# synchronizer_v1_0.net
KiCad netlist of a schematic drawn in EAGLE
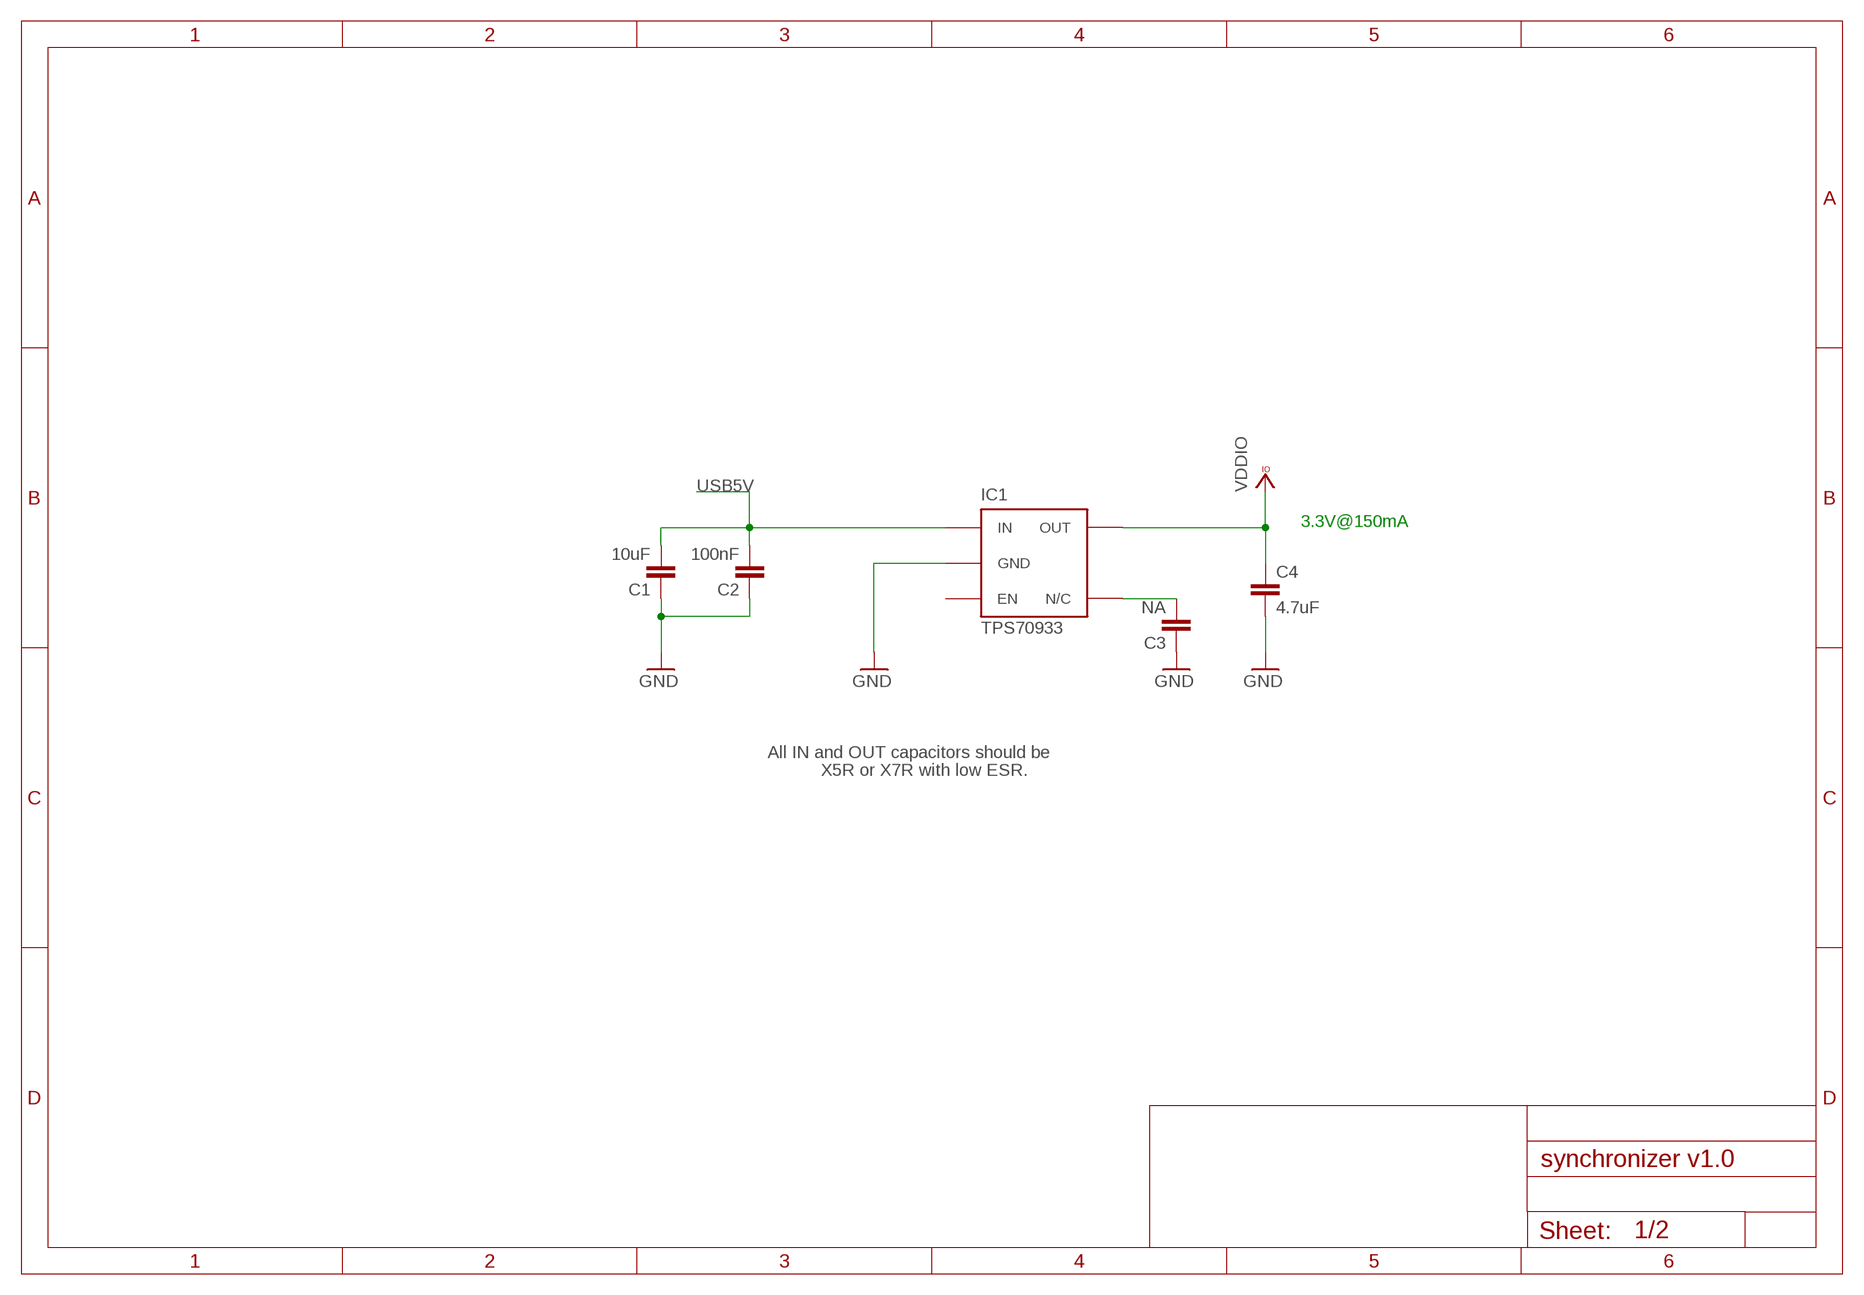
[diagram p0: schematic, sheet 1]
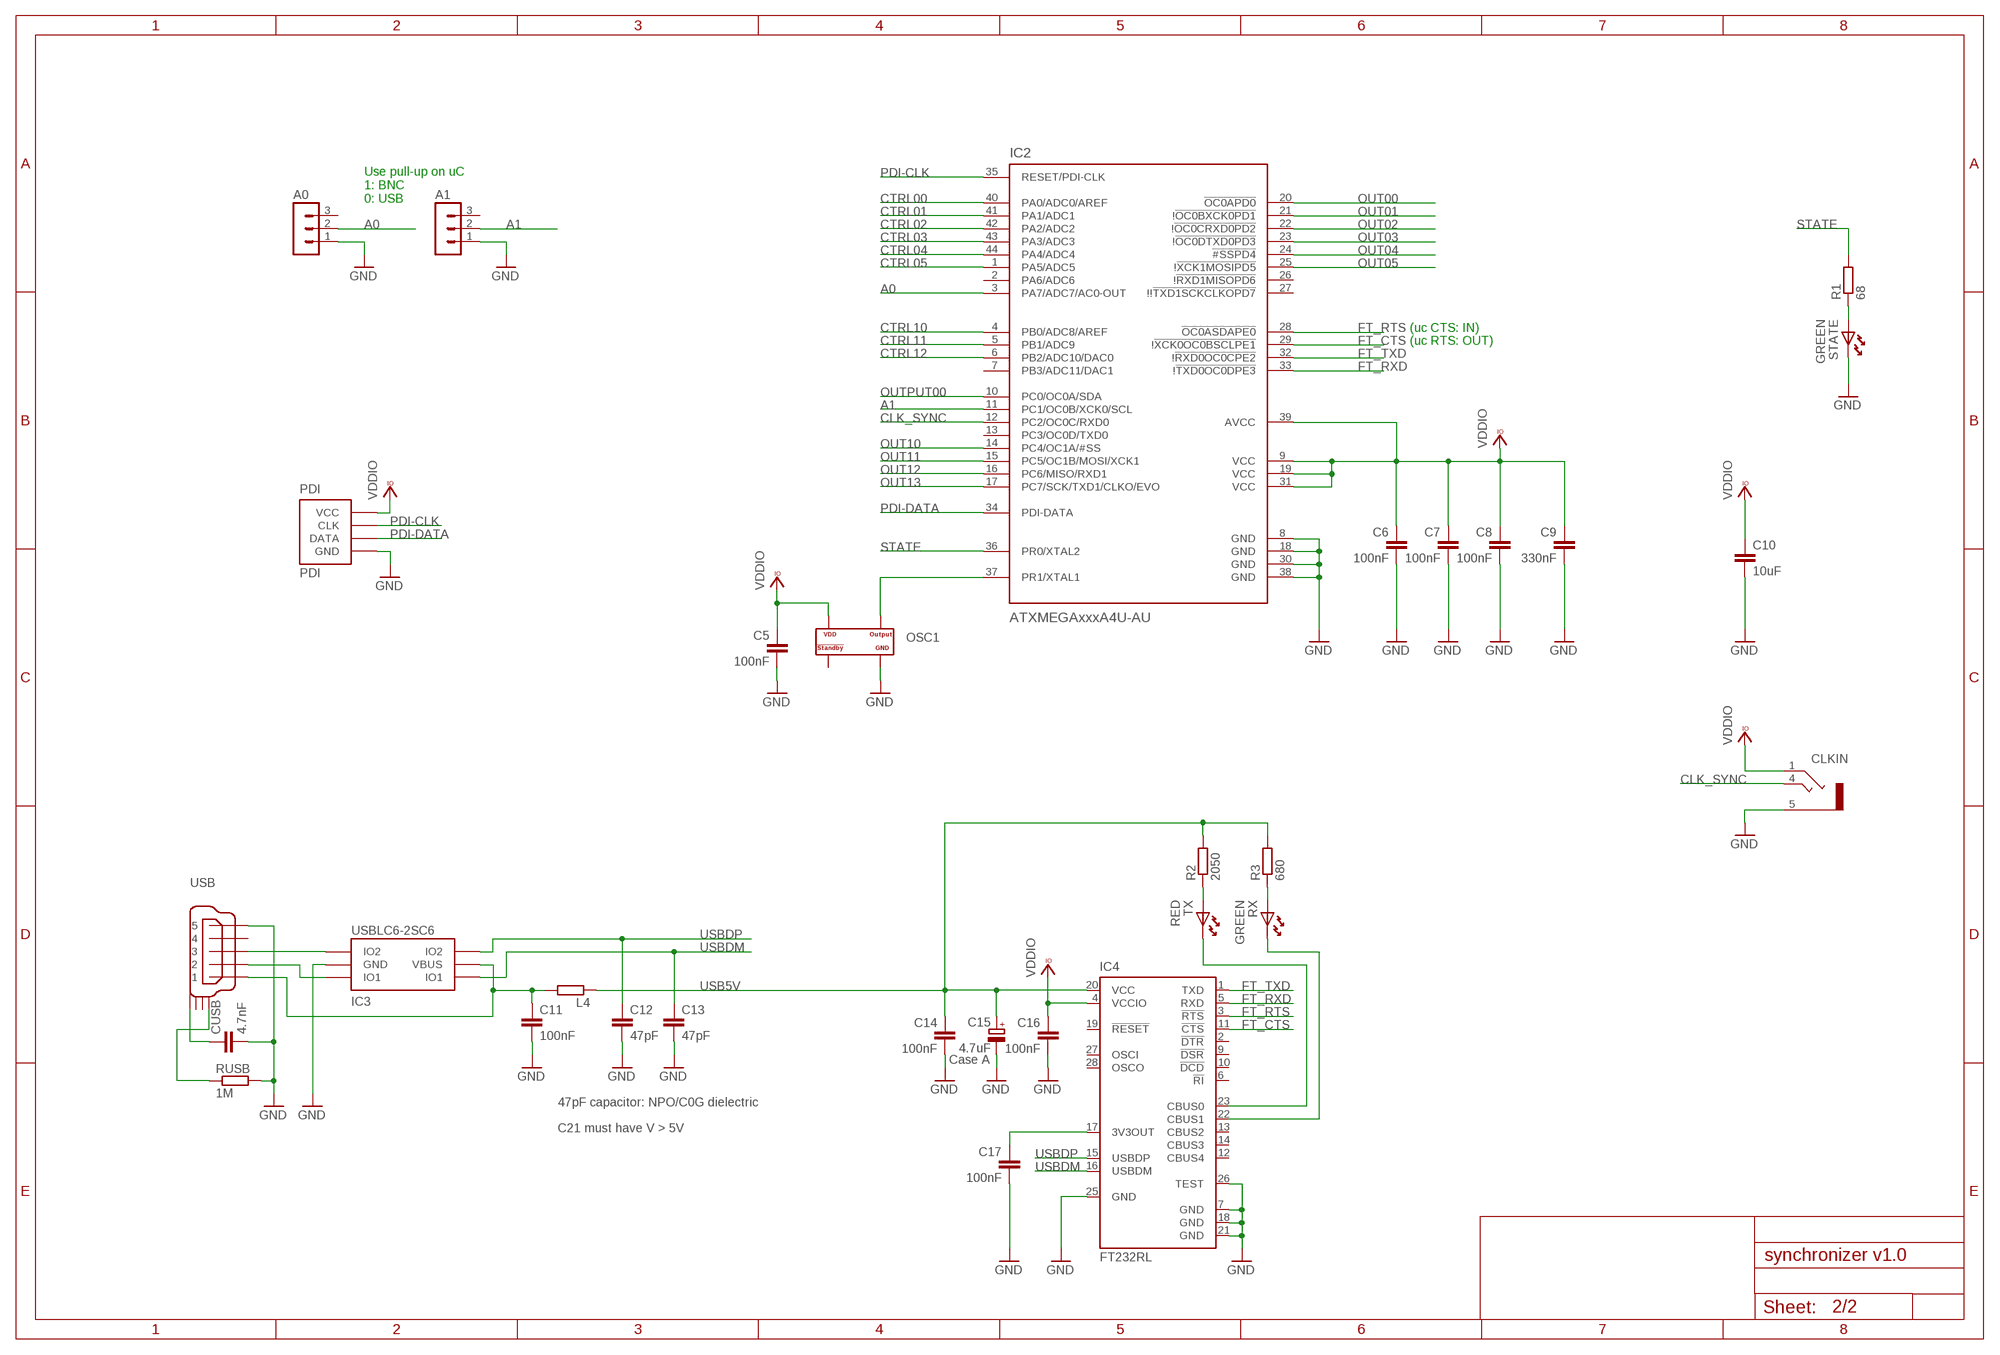
[diagram p1: schematic, sheet 2, part 1 of 2]
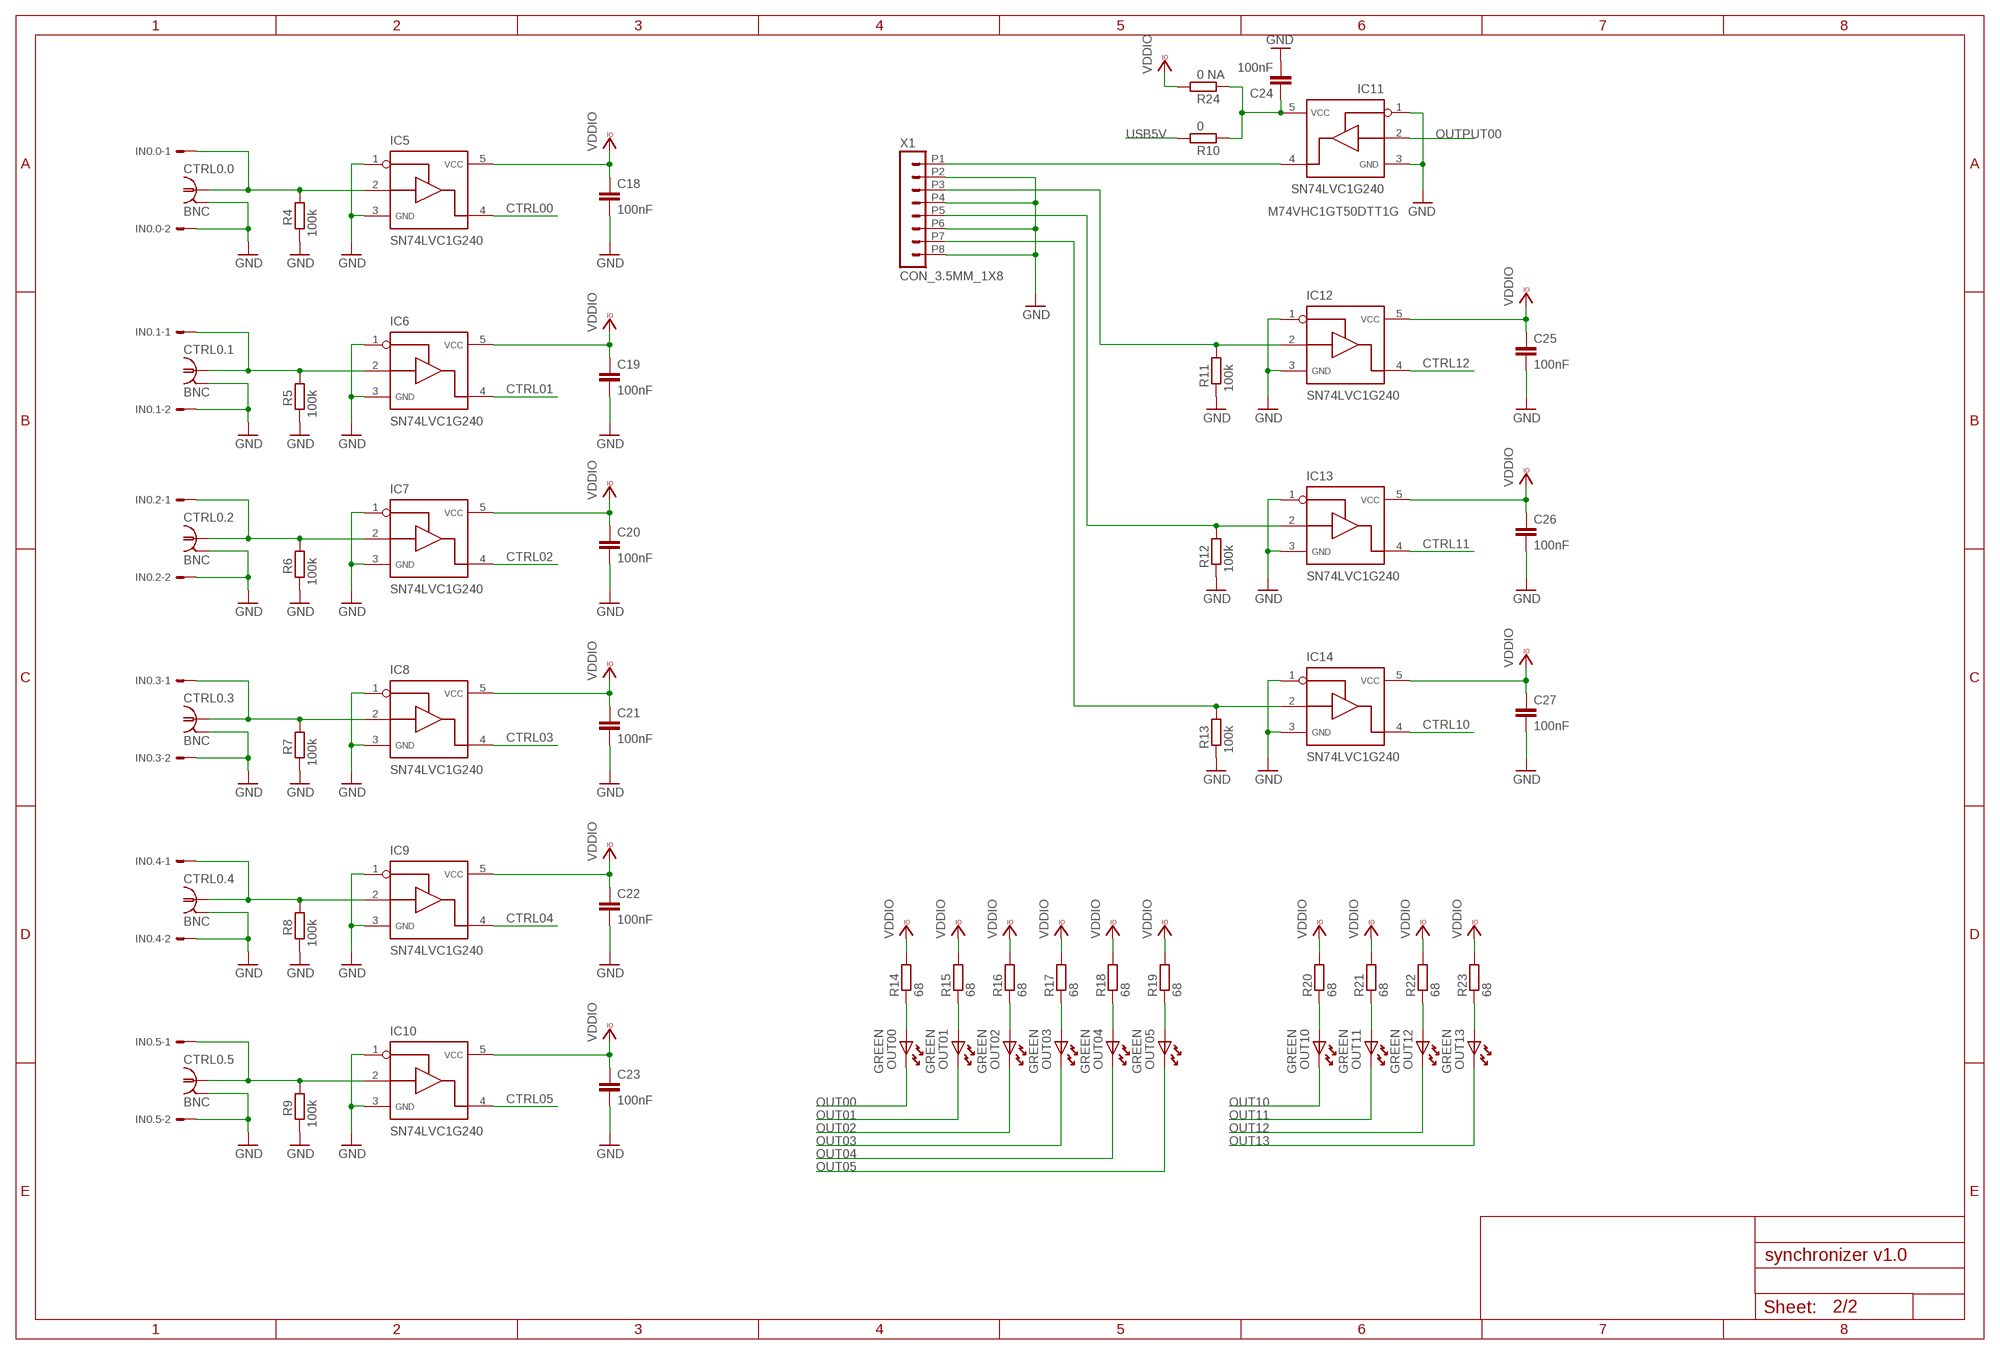
[diagram p2: schematic, sheet 2, part 2 of 2]

(export (version "E")
  (design (tool "Eeschema 10.0.6"))
  (components
    (comp (ref "A0")
      (value "MA03-1")
      (footprint "eagle-import:MA03-1")
      (libsource (lib "eagle-import") (part "MA03-1"))
    )
    (comp (ref "A1")
      (value "MA03-1")
      (footprint "eagle-import:MA03-1")
      (libsource (lib "eagle-import") (part "MA03-1"))
    )
    (comp (ref "C5")
      (value "100nF")
      (footprint "eagle-import:C0402")
      (libsource (lib "eagle-import") (part "C-EUC0402"))
    )
    (comp (ref "C6")
      (value "100nF")
      (footprint "eagle-import:C0402")
      (libsource (lib "eagle-import") (part "C-EUC0402"))
    )
    (comp (ref "C7")
      (value "100nF")
      (footprint "eagle-import:C0402")
      (libsource (lib "eagle-import") (part "C-EUC0402"))
    )
    (comp (ref "C8")
      (value "100nF")
      (footprint "eagle-import:C0402")
      (libsource (lib "eagle-import") (part "C-EUC0402"))
    )
    (comp (ref "C9")
      (value "330nF")
      (footprint "eagle-import:C0402")
      (libsource (lib "eagle-import") (part "C-EUC0402"))
    )
    (comp (ref "C10")
      (value "10uF")
      (footprint "eagle-import:C0603")
      (libsource (lib "eagle-import") (part "C-EUC0603"))
    )
    (comp (ref "C11")
      (value "100nF")
      (footprint "eagle-import:C0402")
      (libsource (lib "eagle-import") (part "C-EUC0402"))
    )
    (comp (ref "C12")
      (value "47pF")
      (footprint "eagle-import:C0402")
      (libsource (lib "eagle-import") (part "C-EUC0402"))
    )
    (comp (ref "C13")
      (value "47pF")
      (footprint "eagle-import:C0402")
      (libsource (lib "eagle-import") (part "C-EUC0402"))
    )
    (comp (ref "C14")
      (value "100nF")
      (footprint "eagle-import:C0402")
      (libsource (lib "eagle-import") (part "C-EUC0402"))
    )
    (comp (ref "C15")
      (value "4.7uF")
      (footprint "eagle-import:A_3216-18W")
      (libsource (lib "eagle-import") (part "CPOL-EUA/3216-18W"))
    )
    (comp (ref "C16")
      (value "100nF")
      (footprint "eagle-import:C0402")
      (libsource (lib "eagle-import") (part "C-EUC0402"))
    )
    (comp (ref "C17")
      (value "100nF")
      (footprint "eagle-import:C0402")
      (libsource (lib "eagle-import") (part "C-EUC0402"))
    )
    (comp (ref "C18")
      (value "100nF")
      (footprint "eagle-import:C0402")
      (libsource (lib "eagle-import") (part "C-EUC0402"))
    )
    (comp (ref "C19")
      (value "100nF")
      (footprint "eagle-import:C0402")
      (libsource (lib "eagle-import") (part "C-EUC0402"))
    )
    (comp (ref "C20")
      (value "100nF")
      (footprint "eagle-import:C0402")
      (libsource (lib "eagle-import") (part "C-EUC0402"))
    )
    (comp (ref "C21")
      (value "100nF")
      (footprint "eagle-import:C0402")
      (libsource (lib "eagle-import") (part "C-EUC0402"))
    )
    (comp (ref "C22")
      (value "100nF")
      (footprint "eagle-import:C0402")
      (libsource (lib "eagle-import") (part "C-EUC0402"))
    )
    (comp (ref "C23")
      (value "100nF")
      (footprint "eagle-import:C0402")
      (libsource (lib "eagle-import") (part "C-EUC0402"))
    )
    (comp (ref "C24")
      (value "100nF")
      (footprint "eagle-import:C0402")
      (libsource (lib "eagle-import") (part "C-EUC0402"))
    )
    (comp (ref "C25")
      (value "100nF")
      (footprint "eagle-import:C0402")
      (libsource (lib "eagle-import") (part "C-EUC0402"))
    )
    (comp (ref "C26")
      (value "100nF")
      (footprint "eagle-import:C0402")
      (libsource (lib "eagle-import") (part "C-EUC0402"))
    )
    (comp (ref "C27")
      (value "100nF")
      (footprint "eagle-import:C0402")
      (libsource (lib "eagle-import") (part "C-EUC0402"))
    )
    (comp (ref "CLKIN")
      (value "STEREO_JACK")
      (footprint "eagle-import:35RASMT2BHNTRX")
      (libsource (lib "eagle-import") (part "STEREO_JACK"))
    )
    (comp (ref "CTRL0.0")
      (value "BNC")
      (footprint "eagle-import:BNC_RA")
      (libsource (lib "eagle-import") (part "BNC"))
    )
    (comp (ref "CTRL0.1")
      (value "BNC")
      (footprint "eagle-import:BNC_RA")
      (libsource (lib "eagle-import") (part "BNC"))
    )
    (comp (ref "CTRL0.2")
      (value "BNC")
      (footprint "eagle-import:BNC_RA")
      (libsource (lib "eagle-import") (part "BNC"))
    )
    (comp (ref "CTRL0.3")
      (value "BNC")
      (footprint "eagle-import:BNC_RA")
      (libsource (lib "eagle-import") (part "BNC"))
    )
    (comp (ref "CTRL0.4")
      (value "BNC")
      (footprint "eagle-import:BNC_RA")
      (libsource (lib "eagle-import") (part "BNC"))
    )
    (comp (ref "CTRL0.5")
      (value "BNC")
      (footprint "eagle-import:BNC_RA")
      (libsource (lib "eagle-import") (part "BNC"))
    )
    (comp (ref "CUSB")
      (value "4.7nF")
      (footprint "eagle-import:C0402")
      (libsource (lib "eagle-import") (part "C-EUC0402"))
    )
    (comp (ref "IC2")
      (value "ATXMEGAxxxA4U-AU")
      (footprint "eagle-import:QFP80P1200X1200X120-44N")
      (libsource (lib "eagle-import") (part "AT-XMEGA-XXA4-AU"))
    )
    (comp (ref "IC3")
      (value "USBLC6-2SC6")
      (footprint "eagle-import:SOT23-6L")
      (libsource (lib "eagle-import") (part "USBLC6-2"))
    )
    (comp (ref "IC4")
      (value "FT232RL")
      (footprint "eagle-import:SSOP28")
      (libsource (lib "eagle-import") (part "FT232RL"))
    )
    (comp (ref "IC5")
      (value "SN74LVC1G240")
      (footprint "eagle-import:SOT23-5")
      (libsource (lib "eagle-import") (part "SN74LVC1G125"))
    )
    (comp (ref "IC6")
      (value "SN74LVC1G240")
      (footprint "eagle-import:SOT23-5")
      (libsource (lib "eagle-import") (part "SN74LVC1G125"))
    )
    (comp (ref "IC7")
      (value "SN74LVC1G240")
      (footprint "eagle-import:SOT23-5")
      (libsource (lib "eagle-import") (part "SN74LVC1G125"))
    )
    (comp (ref "IC8")
      (value "SN74LVC1G240")
      (footprint "eagle-import:SOT23-5")
      (libsource (lib "eagle-import") (part "SN74LVC1G125"))
    )
    (comp (ref "IC9")
      (value "SN74LVC1G240")
      (footprint "eagle-import:SOT23-5")
      (libsource (lib "eagle-import") (part "SN74LVC1G125"))
    )
    (comp (ref "IC10")
      (value "SN74LVC1G240")
      (footprint "eagle-import:SOT23-5")
      (libsource (lib "eagle-import") (part "SN74LVC1G125"))
    )
    (comp (ref "IC11")
      (value "SN74LVC1G240")
      (footprint "eagle-import:SOT23-5")
      (libsource (lib "eagle-import") (part "SN74LVC1G125"))
    )
    (comp (ref "IC12")
      (value "SN74LVC1G240")
      (footprint "eagle-import:SOT23-5")
      (libsource (lib "eagle-import") (part "SN74LVC1G125"))
    )
    (comp (ref "IC13")
      (value "SN74LVC1G240")
      (footprint "eagle-import:SOT23-5")
      (libsource (lib "eagle-import") (part "SN74LVC1G125"))
    )
    (comp (ref "IC14")
      (value "SN74LVC1G240")
      (footprint "eagle-import:SOT23-5")
      (libsource (lib "eagle-import") (part "SN74LVC1G125"))
    )
    (comp (ref "IN0.0")
      (value "22-05-7028-02")
      (footprint "eagle-import:7395-02")
      (libsource (lib "eagle-import") (part "22-?-0205-7028"))
    )
    (comp (ref "IN0.1")
      (value "22-05-7028-02")
      (footprint "eagle-import:7395-02")
      (libsource (lib "eagle-import") (part "22-?-0205-7028"))
    )
    (comp (ref "IN0.2")
      (value "22-05-7028-02")
      (footprint "eagle-import:7395-02")
      (libsource (lib "eagle-import") (part "22-?-0205-7028"))
    )
    (comp (ref "IN0.3")
      (value "22-05-7028-02")
      (footprint "eagle-import:7395-02")
      (libsource (lib "eagle-import") (part "22-?-0205-7028"))
    )
    (comp (ref "IN0.4")
      (value "22-05-7028-02")
      (footprint "eagle-import:7395-02")
      (libsource (lib "eagle-import") (part "22-?-0205-7028"))
    )
    (comp (ref "IN0.5")
      (value "22-05-7028-02")
      (footprint "eagle-import:7395-02")
      (libsource (lib "eagle-import") (part "22-?-0205-7028"))
    )
    (comp (ref "L4")
      (value "???")
      (footprint "eagle-import:R0805")
      (libsource (lib "eagle-import") (part "R-EU_R0805"))
    )
    (comp (ref "OSC1")
      (value "OSCILLATOR")
      (footprint "eagle-import:OSCILLATOR_3.2X2.5")
      (libsource (lib "eagle-import") (part "OSCILLATOR"))
    )
    (comp (ref "OUT00")
      (value "GREEN")
      (footprint "eagle-import:LED_HAND")
      (libsource (lib "eagle-import") (part "LEDHAND"))
    )
    (comp (ref "OUT01")
      (value "GREEN")
      (footprint "eagle-import:LED_HAND")
      (libsource (lib "eagle-import") (part "LEDHAND"))
    )
    (comp (ref "OUT02")
      (value "GREEN")
      (footprint "eagle-import:LED_HAND")
      (libsource (lib "eagle-import") (part "LEDHAND"))
    )
    (comp (ref "OUT03")
      (value "GREEN")
      (footprint "eagle-import:LED_HAND")
      (libsource (lib "eagle-import") (part "LEDHAND"))
    )
    (comp (ref "OUT04")
      (value "GREEN")
      (footprint "eagle-import:LED_HAND")
      (libsource (lib "eagle-import") (part "LEDHAND"))
    )
    (comp (ref "OUT05")
      (value "GREEN")
      (footprint "eagle-import:LED_HAND")
      (libsource (lib "eagle-import") (part "LEDHAND"))
    )
    (comp (ref "OUT10")
      (value "GREEN")
      (footprint "eagle-import:LED_HAND")
      (libsource (lib "eagle-import") (part "LEDHAND"))
    )
    (comp (ref "OUT11")
      (value "GREEN")
      (footprint "eagle-import:LED_HAND")
      (libsource (lib "eagle-import") (part "LEDHAND"))
    )
    (comp (ref "OUT12")
      (value "GREEN")
      (footprint "eagle-import:LED_HAND")
      (libsource (lib "eagle-import") (part "LEDHAND"))
    )
    (comp (ref "OUT13")
      (value "GREEN")
      (footprint "eagle-import:LED_HAND")
      (libsource (lib "eagle-import") (part "LEDHAND"))
    )
    (comp (ref "PDI")
      (value "PDI")
      (footprint "eagle-import:PDI_2.54_1X4")
      (libsource (lib "eagle-import") (part "PDI"))
    )
    (comp (ref "R1")
      (value "68")
      (footprint "eagle-import:R0402")
      (libsource (lib "eagle-import") (part "R-EU_R0402"))
    )
    (comp (ref "R2")
      (value "2050")
      (footprint "eagle-import:R0402")
      (libsource (lib "eagle-import") (part "R-EU_R0402"))
    )
    (comp (ref "R3")
      (value "680")
      (footprint "eagle-import:R0402")
      (libsource (lib "eagle-import") (part "R-EU_R0402"))
    )
    (comp (ref "R4")
      (value "100k")
      (footprint "eagle-import:R0402")
      (libsource (lib "eagle-import") (part "R-EU_R0402"))
    )
    (comp (ref "R5")
      (value "100k")
      (footprint "eagle-import:R0402")
      (libsource (lib "eagle-import") (part "R-EU_R0402"))
    )
    (comp (ref "R6")
      (value "100k")
      (footprint "eagle-import:R0402")
      (libsource (lib "eagle-import") (part "R-EU_R0402"))
    )
    (comp (ref "R7")
      (value "100k")
      (footprint "eagle-import:R0402")
      (libsource (lib "eagle-import") (part "R-EU_R0402"))
    )
    (comp (ref "R8")
      (value "100k")
      (footprint "eagle-import:R0402")
      (libsource (lib "eagle-import") (part "R-EU_R0402"))
    )
    (comp (ref "R9")
      (value "100k")
      (footprint "eagle-import:R0402")
      (libsource (lib "eagle-import") (part "R-EU_R0402"))
    )
    (comp (ref "R10")
      (value "0")
      (footprint "eagle-import:R0402")
      (libsource (lib "eagle-import") (part "R-EU_R0402"))
    )
    (comp (ref "R11")
      (value "100k")
      (footprint "eagle-import:R0402")
      (libsource (lib "eagle-import") (part "R-EU_R0402"))
    )
    (comp (ref "R12")
      (value "100k")
      (footprint "eagle-import:R0402")
      (libsource (lib "eagle-import") (part "R-EU_R0402"))
    )
    (comp (ref "R13")
      (value "100k")
      (footprint "eagle-import:R0402")
      (libsource (lib "eagle-import") (part "R-EU_R0402"))
    )
    (comp (ref "R14")
      (value "68")
      (footprint "eagle-import:R0402")
      (libsource (lib "eagle-import") (part "R-EU_R0402"))
    )
    (comp (ref "R15")
      (value "68")
      (footprint "eagle-import:R0402")
      (libsource (lib "eagle-import") (part "R-EU_R0402"))
    )
    (comp (ref "R16")
      (value "68")
      (footprint "eagle-import:R0402")
      (libsource (lib "eagle-import") (part "R-EU_R0402"))
    )
    (comp (ref "R17")
      (value "68")
      (footprint "eagle-import:R0402")
      (libsource (lib "eagle-import") (part "R-EU_R0402"))
    )
    (comp (ref "R18")
      (value "68")
      (footprint "eagle-import:R0402")
      (libsource (lib "eagle-import") (part "R-EU_R0402"))
    )
    (comp (ref "R19")
      (value "68")
      (footprint "eagle-import:R0402")
      (libsource (lib "eagle-import") (part "R-EU_R0402"))
    )
    (comp (ref "R20")
      (value "68")
      (footprint "eagle-import:R0402")
      (libsource (lib "eagle-import") (part "R-EU_R0402"))
    )
    (comp (ref "R21")
      (value "68")
      (footprint "eagle-import:R0402")
      (libsource (lib "eagle-import") (part "R-EU_R0402"))
    )
    (comp (ref "R22")
      (value "68")
      (footprint "eagle-import:R0402")
      (libsource (lib "eagle-import") (part "R-EU_R0402"))
    )
    (comp (ref "R23")
      (value "68")
      (footprint "eagle-import:R0402")
      (libsource (lib "eagle-import") (part "R-EU_R0402"))
    )
    (comp (ref "R24")
      (value "0 NA")
      (footprint "eagle-import:R0402")
      (libsource (lib "eagle-import") (part "R-EU_R0402"))
    )
    (comp (ref "RUSB")
      (value "1M")
      (footprint "eagle-import:R0603")
      (libsource (lib "eagle-import") (part "R-EU_R0603"))
    )
    (comp (ref "RX")
      (value "GREEN")
      (footprint "eagle-import:LED_HAND")
      (libsource (lib "eagle-import") (part "LEDHAND"))
    )
    (comp (ref "STATE")
      (value "GREEN")
      (footprint "eagle-import:LED_HAND")
      (libsource (lib "eagle-import") (part "LEDHAND"))
    )
    (comp (ref "TX")
      (value "RED")
      (footprint "eagle-import:LED_HAND")
      (libsource (lib "eagle-import") (part "LEDHAND"))
    )
    (comp (ref "USB")
      (value "USB_MINI_B")
      (footprint "eagle-import:240-0002-1")
      (libsource (lib "eagle-import") (part "USB_MINI_B"))
    )
    (comp (ref "X1")
      (value "CON_3.5MM_1X8")
      (footprint "eagle-import:CON_3.5MM_1X8")
      (libsource (lib "eagle-import") (part "CON_3.5MM_1X8"))
    )
    (comp (ref "C1")
      (value "10uF")
      (footprint "eagle-import:C0603")
      (libsource (lib "eagle-import") (part "C-EUC0603"))
    )
    (comp (ref "C2")
      (value "100nF")
      (footprint "eagle-import:C0402")
      (libsource (lib "eagle-import") (part "C-EUC0402"))
    )
    (comp (ref "C3")
      (value "NA")
      (footprint "eagle-import:C0402")
      (libsource (lib "eagle-import") (part "C-EUC0402"))
    )
    (comp (ref "C4")
      (value "4.7uF")
      (footprint "eagle-import:C0603")
      (libsource (lib "eagle-import") (part "C-EUC0603"))
    )
    (comp (ref "IC1")
      (value "TPS70933")
      (footprint "eagle-import:TSOT23-5")
      (libsource (lib "eagle-import") (part "TLV700XX"))
    )
  )
  (nets
    (net (code "1") (name "A0") (class "Default")
      (node (ref "A0") (pin "2") (pinfunction "2_2") (pintype "passive"))
      (node (ref "IC2") (pin "3") (pinfunction "PA7/ADC7/AC0-OUT_3") (pintype "bidirectional"))
    )
    (net (code "2") (name "A1") (class "Default")
      (node (ref "A1") (pin "2") (pinfunction "2_2") (pintype "passive"))
      (node (ref "IC2") (pin "11") (pinfunction "PC1/OC0B/XCK0/SCL_11") (pintype "bidirectional"))
    )
    (net (code "3") (name "CLK_SYNC") (class "Default")
      (node (ref "CLKIN") (pin "4") (pinfunction "4_4") (pintype "passive"))
      (node (ref "IC2") (pin "12") (pinfunction "PC2/OC0C/RXD0_12") (pintype "bidirectional"))
    )
    (net (code "4") (name "CTRL00") (class "Default")
      (node (ref "IC2") (pin "40") (pinfunction "PA0/ADC0/AREF_40") (pintype "bidirectional"))
      (node (ref "IC5") (pin "4") (pinfunction "P$4_4") (pintype "bidirectional"))
    )
    (net (code "5") (name "CTRL01") (class "Default")
      (node (ref "IC2") (pin "41") (pinfunction "PA1/ADC1_41") (pintype "bidirectional"))
      (node (ref "IC6") (pin "4") (pinfunction "P$4_4") (pintype "bidirectional"))
    )
    (net (code "6") (name "CTRL02") (class "Default")
      (node (ref "IC2") (pin "42") (pinfunction "PA2/ADC2_42") (pintype "bidirectional"))
      (node (ref "IC7") (pin "4") (pinfunction "P$4_4") (pintype "bidirectional"))
    )
    (net (code "7") (name "CTRL03") (class "Default")
      (node (ref "IC2") (pin "43") (pinfunction "PA3/ADC3_43") (pintype "bidirectional"))
      (node (ref "IC8") (pin "4") (pinfunction "P$4_4") (pintype "bidirectional"))
    )
    (net (code "8") (name "CTRL04") (class "Default")
      (node (ref "IC2") (pin "44") (pinfunction "PA4/ADC4_44") (pintype "bidirectional"))
      (node (ref "IC9") (pin "4") (pinfunction "P$4_4") (pintype "bidirectional"))
    )
    (net (code "9") (name "CTRL05") (class "Default")
      (node (ref "IC10") (pin "4") (pinfunction "P$4_4") (pintype "bidirectional"))
      (node (ref "IC2") (pin "1") (pinfunction "PA5/ADC5_1") (pintype "bidirectional"))
    )
    (net (code "10") (name "CTRL10") (class "Default")
      (node (ref "IC14") (pin "4") (pinfunction "P$4_4") (pintype "bidirectional"))
      (node (ref "IC2") (pin "4") (pinfunction "PB0/ADC8/AREF_4") (pintype "bidirectional"))
    )
    (net (code "11") (name "CTRL11") (class "Default")
      (node (ref "IC13") (pin "4") (pinfunction "P$4_4") (pintype "bidirectional"))
      (node (ref "IC2") (pin "5") (pinfunction "PB1/ADC9_5") (pintype "bidirectional"))
    )
    (net (code "12") (name "CTRL12") (class "Default")
      (node (ref "IC12") (pin "4") (pinfunction "P$4_4") (pintype "bidirectional"))
      (node (ref "IC2") (pin "6") (pinfunction "PB2/ADC10/DAC0_6") (pintype "bidirectional"))
    )
    (net (code "13") (name "FT_CTS") (class "Default")
      (node (ref "IC2") (pin "29") (pinfunction "~XCK0OC0BSCLPE1_29") (pintype "bidirectional"))
      (node (ref "IC4") (pin "11") (pinfunction "~{CTS}_11") (pintype "input"))
    )
    (net (code "14") (name "FT_RTS") (class "Default")
      (node (ref "IC2") (pin "28") (pinfunction "~{OC0ASDAPE0}_28") (pintype "bidirectional"))
      (node (ref "IC4") (pin "3") (pinfunction "~{RTS}_3") (pintype "output"))
    )
    (net (code "15") (name "FT_RXD") (class "Default")
      (node (ref "IC2") (pin "33") (pinfunction "~TXD0OC0DPE3_33") (pintype "bidirectional"))
      (node (ref "IC4") (pin "5") (pinfunction "RXD_5") (pintype "input"))
    )
    (net (code "16") (name "FT_TXD") (class "Default")
      (node (ref "IC2") (pin "32") (pinfunction "~RXD0OC0CPE2_32") (pintype "bidirectional"))
      (node (ref "IC4") (pin "1") (pinfunction "TXD_1") (pintype "output"))
    )
    (net (code "17") (name "GND") (class "Default")
      (node (ref "A0") (pin "1") (pinfunction "1_1") (pintype "passive"))
      (node (ref "A1") (pin "1") (pinfunction "1_1") (pintype "passive"))
      (node (ref "C1") (pin "1") (pinfunction "1_1") (pintype "passive"))
      (node (ref "C10") (pin "2") (pinfunction "2_2") (pintype "passive"))
      (node (ref "C11") (pin "2") (pinfunction "2_2") (pintype "passive"))
      (node (ref "C12") (pin "2") (pinfunction "2_2") (pintype "passive"))
      (node (ref "C13") (pin "2") (pinfunction "2_2") (pintype "passive"))
      (node (ref "C14") (pin "2") (pinfunction "2_2") (pintype "passive"))
      (node (ref "C15") (pin "-") (pinfunction "-_-") (pintype "passive"))
      (node (ref "C16") (pin "2") (pinfunction "2_2") (pintype "passive"))
      (node (ref "C17") (pin "2") (pinfunction "2_2") (pintype "passive"))
      (node (ref "C18") (pin "2") (pinfunction "2_2") (pintype "passive"))
      (node (ref "C19") (pin "2") (pinfunction "2_2") (pintype "passive"))
      (node (ref "C2") (pin "1") (pinfunction "1_1") (pintype "passive"))
      (node (ref "C20") (pin "2") (pinfunction "2_2") (pintype "passive"))
      (node (ref "C21") (pin "2") (pinfunction "2_2") (pintype "passive"))
      (node (ref "C22") (pin "2") (pinfunction "2_2") (pintype "passive"))
      (node (ref "C23") (pin "2") (pinfunction "2_2") (pintype "passive"))
      (node (ref "C24") (pin "2") (pinfunction "2_2") (pintype "passive"))
      (node (ref "C25") (pin "2") (pinfunction "2_2") (pintype "passive"))
      (node (ref "C26") (pin "2") (pinfunction "2_2") (pintype "passive"))
      (node (ref "C27") (pin "2") (pinfunction "2_2") (pintype "passive"))
      (node (ref "C3") (pin "1") (pinfunction "1_1") (pintype "passive"))
      (node (ref "C4") (pin "2") (pinfunction "2_2") (pintype "passive"))
      (node (ref "C5") (pin "2") (pinfunction "2_2") (pintype "passive"))
      (node (ref "C6") (pin "2") (pinfunction "2_2") (pintype "passive"))
      (node (ref "C7") (pin "2") (pinfunction "2_2") (pintype "passive"))
      (node (ref "C8") (pin "2") (pinfunction "2_2") (pintype "passive"))
      (node (ref "C9") (pin "2") (pinfunction "2_2") (pintype "passive"))
      (node (ref "CLKIN") (pin "5") (pinfunction "5_5") (pintype "passive"))
      (node (ref "CTRL0.0") (pin "2") (pinfunction "2_2") (pintype "passive"))
      (node (ref "CTRL0.1") (pin "2") (pinfunction "2_2") (pintype "passive"))
      (node (ref "CTRL0.2") (pin "2") (pinfunction "2_2") (pintype "passive"))
      (node (ref "CTRL0.3") (pin "2") (pinfunction "2_2") (pintype "passive"))
      (node (ref "CTRL0.4") (pin "2") (pinfunction "2_2") (pintype "passive"))
      (node (ref "CTRL0.5") (pin "2") (pinfunction "2_2") (pintype "passive"))
      (node (ref "CUSB") (pin "2") (pinfunction "2_2") (pintype "passive"))
      (node (ref "IC1") (pin "2") (pinfunction "GND_2") (pintype "bidirectional"))
      (node (ref "IC10") (pin "1") (pinfunction "P$1_1") (pintype "bidirectional"))
      (node (ref "IC10") (pin "3") (pinfunction "P$3_3") (pintype "bidirectional"))
      (node (ref "IC11") (pin "1") (pinfunction "P$1_1") (pintype "bidirectional"))
      (node (ref "IC11") (pin "3") (pinfunction "P$3_3") (pintype "bidirectional"))
      (node (ref "IC12") (pin "1") (pinfunction "P$1_1") (pintype "bidirectional"))
      (node (ref "IC12") (pin "3") (pinfunction "P$3_3") (pintype "bidirectional"))
      (node (ref "IC13") (pin "1") (pinfunction "P$1_1") (pintype "bidirectional"))
      (node (ref "IC13") (pin "3") (pinfunction "P$3_3") (pintype "bidirectional"))
      (node (ref "IC14") (pin "1") (pinfunction "P$1_1") (pintype "bidirectional"))
      (node (ref "IC14") (pin "3") (pinfunction "P$3_3") (pintype "bidirectional"))
      (node (ref "IC2") (pin "18") (pinfunction "GND_18") (pintype "power_in"))
      (node (ref "IC2") (pin "30") (pinfunction "GND_30") (pintype "power_in"))
      (node (ref "IC2") (pin "38") (pinfunction "GND_38") (pintype "power_in"))
      (node (ref "IC2") (pin "8") (pinfunction "GND_8") (pintype "power_in"))
      (node (ref "IC3") (pin "P$2") (pinfunction "GND_P$2") (pintype "bidirectional"))
      (node (ref "IC4") (pin "18") (pinfunction "GND_18") (pintype "power_in"))
      (node (ref "IC4") (pin "21") (pinfunction "GND_21") (pintype "power_in"))
      (node (ref "IC4") (pin "25") (pinfunction "GND_25") (pintype "power_in"))
      (node (ref "IC4") (pin "26") (pinfunction "TEST_26") (pintype "input"))
      (node (ref "IC4") (pin "7") (pinfunction "GND_7") (pintype "power_in"))
      (node (ref "IC5") (pin "1") (pinfunction "P$1_1") (pintype "bidirectional"))
      (node (ref "IC5") (pin "3") (pinfunction "P$3_3") (pintype "bidirectional"))
      (node (ref "IC6") (pin "1") (pinfunction "P$1_1") (pintype "bidirectional"))
      (node (ref "IC6") (pin "3") (pinfunction "P$3_3") (pintype "bidirectional"))
      (node (ref "IC7") (pin "1") (pinfunction "P$1_1") (pintype "bidirectional"))
      (node (ref "IC7") (pin "3") (pinfunction "P$3_3") (pintype "bidirectional"))
      (node (ref "IC8") (pin "1") (pinfunction "P$1_1") (pintype "bidirectional"))
      (node (ref "IC8") (pin "3") (pinfunction "P$3_3") (pintype "bidirectional"))
      (node (ref "IC9") (pin "1") (pinfunction "P$1_1") (pintype "bidirectional"))
      (node (ref "IC9") (pin "3") (pinfunction "P$3_3") (pintype "bidirectional"))
      (node (ref "IN0.0") (pin "2") (pinfunction "S_2") (pintype "passive"))
      (node (ref "IN0.1") (pin "2") (pinfunction "S_2") (pintype "passive"))
      (node (ref "IN0.2") (pin "2") (pinfunction "S_2") (pintype "passive"))
      (node (ref "IN0.3") (pin "2") (pinfunction "S_2") (pintype "passive"))
      (node (ref "IN0.4") (pin "2") (pinfunction "S_2") (pintype "passive"))
      (node (ref "IN0.5") (pin "2") (pinfunction "S_2") (pintype "passive"))
      (node (ref "OSC1") (pin "P$2") (pinfunction "GND_P$2") (pintype "passive"))
      (node (ref "PDI") (pin "P$1") (pinfunction "GND_P$1") (pintype "bidirectional"))
      (node (ref "R11") (pin "2") (pinfunction "2_2") (pintype "passive"))
      (node (ref "R12") (pin "2") (pinfunction "2_2") (pintype "passive"))
      (node (ref "R13") (pin "2") (pinfunction "2_2") (pintype "passive"))
      (node (ref "R4") (pin "2") (pinfunction "2_2") (pintype "passive"))
      (node (ref "R5") (pin "2") (pinfunction "2_2") (pintype "passive"))
      (node (ref "R6") (pin "2") (pinfunction "2_2") (pintype "passive"))
      (node (ref "R7") (pin "2") (pinfunction "2_2") (pintype "passive"))
      (node (ref "R8") (pin "2") (pinfunction "2_2") (pintype "passive"))
      (node (ref "R9") (pin "2") (pinfunction "2_2") (pintype "passive"))
      (node (ref "RUSB") (pin "2") (pinfunction "2_2") (pintype "passive"))
      (node (ref "STATE") (pin "K") (pinfunction "K_K") (pintype "bidirectional"))
      (node (ref "USB") (pin "P$5") (pinfunction "5_P$5") (pintype "bidirectional"))
      (node (ref "X1") (pin "P2") (pinfunction "2_P2") (pintype "passive"))
      (node (ref "X1") (pin "P4") (pinfunction "4_P4") (pintype "passive"))
      (node (ref "X1") (pin "P6") (pinfunction "6_P6") (pintype "passive"))
      (node (ref "X1") (pin "P8") (pinfunction "8_P8") (pintype "passive"))
    )
    (net (code "18") (name "Net-(IC1-N{slash}C)") (class "Default")
      (node (ref "C3") (pin "2") (pinfunction "2_2") (pintype "passive"))
      (node (ref "IC1") (pin "4") (pinfunction "N/C_4") (pintype "bidirectional"))
    )
    (net (code "19") (name "Net-(IC2-PR1{slash}XTAL1)") (class "Default")
      (node (ref "IC2") (pin "37") (pinfunction "PR1/XTAL1_37") (pintype "bidirectional"))
      (node (ref "OSC1") (pin "P$3") (pinfunction "OUTPUT_P$3") (pintype "passive"))
    )
    (net (code "20") (name "Net-(IC3-VBUS)") (class "Default")
      (node (ref "C11") (pin "1") (pinfunction "1_1") (pintype "passive"))
      (node (ref "IC3") (pin "P$5") (pinfunction "VBUS_P$5") (pintype "bidirectional"))
      (node (ref "L4") (pin "2") (pinfunction "2_2") (pintype "passive"))
      (node (ref "USB") (pin "P$1") (pinfunction "1_P$1") (pintype "bidirectional"))
    )
    (net (code "21") (name "Net-(IC4-3V3OUT)") (class "Default")
      (node (ref "C17") (pin "1") (pinfunction "1_1") (pintype "passive"))
      (node (ref "IC4") (pin "17") (pinfunction "3V3OUT_17") (pintype "output"))
    )
    (net (code "22") (name "Net-(IC4-CBUS0)") (class "Default")
      (node (ref "IC4") (pin "23") (pinfunction "CBUS0_23") (pintype "bidirectional"))
      (node (ref "TX") (pin "K") (pinfunction "K_K") (pintype "bidirectional"))
    )
    (net (code "23") (name "Net-(IC4-CBUS1)") (class "Default")
      (node (ref "IC4") (pin "22") (pinfunction "CBUS1_22") (pintype "bidirectional"))
      (node (ref "RX") (pin "K") (pinfunction "K_K") (pintype "bidirectional"))
    )
    (net (code "24") (name "Net-(IC5-P$2)") (class "Default")
      (node (ref "CTRL0.0") (pin "1") (pinfunction "1_1") (pintype "passive"))
      (node (ref "IC5") (pin "2") (pinfunction "P$2_2") (pintype "bidirectional"))
      (node (ref "IN0.0") (pin "1") (pinfunction "S_1") (pintype "passive"))
      (node (ref "R4") (pin "1") (pinfunction "1_1") (pintype "passive"))
    )
    (net (code "25") (name "Net-(IC6-P$2)") (class "Default")
      (node (ref "CTRL0.1") (pin "1") (pinfunction "1_1") (pintype "passive"))
      (node (ref "IC6") (pin "2") (pinfunction "P$2_2") (pintype "bidirectional"))
      (node (ref "IN0.1") (pin "1") (pinfunction "S_1") (pintype "passive"))
      (node (ref "R5") (pin "1") (pinfunction "1_1") (pintype "passive"))
    )
    (net (code "26") (name "Net-(IC7-P$2)") (class "Default")
      (node (ref "CTRL0.2") (pin "1") (pinfunction "1_1") (pintype "passive"))
      (node (ref "IC7") (pin "2") (pinfunction "P$2_2") (pintype "bidirectional"))
      (node (ref "IN0.2") (pin "1") (pinfunction "S_1") (pintype "passive"))
      (node (ref "R6") (pin "1") (pinfunction "1_1") (pintype "passive"))
    )
    (net (code "27") (name "Net-(IC8-P$2)") (class "Default")
      (node (ref "CTRL0.3") (pin "1") (pinfunction "1_1") (pintype "passive"))
      (node (ref "IC8") (pin "2") (pinfunction "P$2_2") (pintype "bidirectional"))
      (node (ref "IN0.3") (pin "1") (pinfunction "S_1") (pintype "passive"))
      (node (ref "R7") (pin "1") (pinfunction "1_1") (pintype "passive"))
    )
    (net (code "28") (name "Net-(IC9-P$2)") (class "Default")
      (node (ref "CTRL0.4") (pin "1") (pinfunction "1_1") (pintype "passive"))
      (node (ref "IC9") (pin "2") (pinfunction "P$2_2") (pintype "bidirectional"))
      (node (ref "IN0.4") (pin "1") (pinfunction "S_1") (pintype "passive"))
      (node (ref "R8") (pin "1") (pinfunction "1_1") (pintype "passive"))
    )
    (net (code "29") (name "Net-(IC10-P$2)") (class "Default")
      (node (ref "CTRL0.5") (pin "1") (pinfunction "1_1") (pintype "passive"))
      (node (ref "IC10") (pin "2") (pinfunction "P$2_2") (pintype "bidirectional"))
      (node (ref "IN0.5") (pin "1") (pinfunction "S_1") (pintype "passive"))
      (node (ref "R9") (pin "1") (pinfunction "1_1") (pintype "passive"))
    )
    (net (code "30") (name "Net-(IC11-P$4)") (class "Default")
      (node (ref "IC11") (pin "4") (pinfunction "P$4_4") (pintype "bidirectional"))
      (node (ref "X1") (pin "P1") (pinfunction "1_P1") (pintype "passive"))
    )
    (net (code "31") (name "Net-(IC11-P$5)") (class "Default")
      (node (ref "C24") (pin "1") (pinfunction "1_1") (pintype "passive"))
      (node (ref "IC11") (pin "5") (pinfunction "P$5_5") (pintype "bidirectional"))
      (node (ref "R10") (pin "2") (pinfunction "2_2") (pintype "passive"))
      (node (ref "R24") (pin "2") (pinfunction "2_2") (pintype "passive"))
    )
    (net (code "32") (name "Net-(IC12-P$2)") (class "Default")
      (node (ref "IC12") (pin "2") (pinfunction "P$2_2") (pintype "bidirectional"))
      (node (ref "R11") (pin "1") (pinfunction "1_1") (pintype "passive"))
      (node (ref "X1") (pin "P3") (pinfunction "3_P3") (pintype "passive"))
    )
    (net (code "33") (name "Net-(IC13-P$2)") (class "Default")
      (node (ref "IC13") (pin "2") (pinfunction "P$2_2") (pintype "bidirectional"))
      (node (ref "R12") (pin "1") (pinfunction "1_1") (pintype "passive"))
      (node (ref "X1") (pin "P5") (pinfunction "5_P5") (pintype "passive"))
    )
    (net (code "34") (name "Net-(IC14-P$2)") (class "Default")
      (node (ref "IC14") (pin "2") (pinfunction "P$2_2") (pintype "bidirectional"))
      (node (ref "R13") (pin "1") (pinfunction "1_1") (pintype "passive"))
      (node (ref "X1") (pin "P7") (pinfunction "7_P7") (pintype "passive"))
    )
    (net (code "35") (name "Net-(OUT00-PadA)") (class "Default")
      (node (ref "OUT00") (pin "A") (pinfunction "A_A") (pintype "bidirectional"))
      (node (ref "R14") (pin "1") (pinfunction "1_1") (pintype "passive"))
    )
    (net (code "36") (name "Net-(OUT01-PadA)") (class "Default")
      (node (ref "OUT01") (pin "A") (pinfunction "A_A") (pintype "bidirectional"))
      (node (ref "R15") (pin "1") (pinfunction "1_1") (pintype "passive"))
    )
    (net (code "37") (name "Net-(OUT02-PadA)") (class "Default")
      (node (ref "OUT02") (pin "A") (pinfunction "A_A") (pintype "bidirectional"))
      (node (ref "R16") (pin "1") (pinfunction "1_1") (pintype "passive"))
    )
    (net (code "38") (name "Net-(OUT03-PadA)") (class "Default")
      (node (ref "OUT03") (pin "A") (pinfunction "A_A") (pintype "bidirectional"))
      (node (ref "R17") (pin "1") (pinfunction "1_1") (pintype "passive"))
    )
    (net (code "39") (name "Net-(OUT04-PadA)") (class "Default")
      (node (ref "OUT04") (pin "A") (pinfunction "A_A") (pintype "bidirectional"))
      (node (ref "R18") (pin "1") (pinfunction "1_1") (pintype "passive"))
    )
    (net (code "40") (name "Net-(OUT05-PadA)") (class "Default")
      (node (ref "OUT05") (pin "A") (pinfunction "A_A") (pintype "bidirectional"))
      (node (ref "R19") (pin "1") (pinfunction "1_1") (pintype "passive"))
    )
    (net (code "41") (name "Net-(OUT10-PadA)") (class "Default")
      (node (ref "OUT10") (pin "A") (pinfunction "A_A") (pintype "bidirectional"))
      (node (ref "R20") (pin "1") (pinfunction "1_1") (pintype "passive"))
    )
    (net (code "42") (name "Net-(OUT11-PadA)") (class "Default")
      (node (ref "OUT11") (pin "A") (pinfunction "A_A") (pintype "bidirectional"))
      (node (ref "R21") (pin "1") (pinfunction "1_1") (pintype "passive"))
    )
    (net (code "43") (name "Net-(OUT12-PadA)") (class "Default")
      (node (ref "OUT12") (pin "A") (pinfunction "A_A") (pintype "bidirectional"))
      (node (ref "R22") (pin "1") (pinfunction "1_1") (pintype "passive"))
    )
    (net (code "44") (name "Net-(OUT13-PadA)") (class "Default")
      (node (ref "OUT13") (pin "A") (pinfunction "A_A") (pintype "bidirectional"))
      (node (ref "R23") (pin "1") (pinfunction "1_1") (pintype "passive"))
    )
    (net (code "45") (name "Net-(R1-Pad1)") (class "Default")
      (node (ref "R1") (pin "1") (pinfunction "1_1") (pintype "passive"))
      (node (ref "STATE") (pin "A") (pinfunction "A_A") (pintype "bidirectional"))
    )
    (net (code "46") (name "Net-(R2-Pad1)") (class "Default")
      (node (ref "R2") (pin "1") (pinfunction "1_1") (pintype "passive"))
      (node (ref "TX") (pin "A") (pinfunction "A_A") (pintype "bidirectional"))
    )
    (net (code "47") (name "Net-(R3-Pad1)") (class "Default")
      (node (ref "R3") (pin "1") (pinfunction "1_1") (pintype "passive"))
      (node (ref "RX") (pin "A") (pinfunction "A_A") (pintype "bidirectional"))
    )
    (net (code "48") (name "Net-(USB-2)") (class "Default")
      (node (ref "IC3") (pin "P$1") (pinfunction "IO1_P$1") (pintype "bidirectional"))
      (node (ref "USB") (pin "P$2") (pinfunction "2_P$2") (pintype "bidirectional"))
    )
    (net (code "49") (name "Net-(USB-3)") (class "Default")
      (node (ref "IC3") (pin "P$3") (pinfunction "IO2_P$3") (pintype "bidirectional"))
      (node (ref "USB") (pin "P$3") (pinfunction "3_P$3") (pintype "bidirectional"))
    )
    (net (code "50") (name "Net-(USB-P$1)") (class "Default")
      (node (ref "RUSB") (pin "1") (pinfunction "1_1") (pintype "passive"))
      (node (ref "USB") (pin "SHIELD_1") (pinfunction "P$1_SHIELD_1") (pintype "bidirectional"))
    )
    (net (code "51") (name "Net-(USB-P$4)") (class "Default")
      (node (ref "CUSB") (pin "1") (pinfunction "1_1") (pintype "passive"))
      (node (ref "USB") (pin "SHIELD_4") (pinfunction "P$4_SHIELD_4") (pintype "bidirectional"))
    )
    (net (code "52") (name "OUT00") (class "Default")
      (node (ref "IC2") (pin "20") (pinfunction "~{OC0APD0}_20") (pintype "bidirectional"))
      (node (ref "OUT00") (pin "K") (pinfunction "K_K") (pintype "bidirectional"))
    )
    (net (code "53") (name "OUT01") (class "Default")
      (node (ref "IC2") (pin "21") (pinfunction "~OC0BXCK0PD1_21") (pintype "bidirectional"))
      (node (ref "OUT01") (pin "K") (pinfunction "K_K") (pintype "bidirectional"))
    )
    (net (code "54") (name "OUT02") (class "Default")
      (node (ref "IC2") (pin "22") (pinfunction "~OC0CRXD0PD2_22") (pintype "bidirectional"))
      (node (ref "OUT02") (pin "K") (pinfunction "K_K") (pintype "bidirectional"))
    )
    (net (code "55") (name "OUT03") (class "Default")
      (node (ref "IC2") (pin "23") (pinfunction "~OC0DTXD0PD3_23") (pintype "bidirectional"))
      (node (ref "OUT03") (pin "K") (pinfunction "K_K") (pintype "bidirectional"))
    )
    (net (code "56") (name "OUT04") (class "Default")
      (node (ref "IC2") (pin "24") (pinfunction "~{#SSPD4}_24") (pintype "bidirectional"))
      (node (ref "OUT04") (pin "K") (pinfunction "K_K") (pintype "bidirectional"))
    )
    (net (code "57") (name "OUT05") (class "Default")
      (node (ref "IC2") (pin "25") (pinfunction "~XCK1MOSIPD5_25") (pintype "bidirectional"))
      (node (ref "OUT05") (pin "K") (pinfunction "K_K") (pintype "bidirectional"))
    )
    (net (code "58") (name "OUT10") (class "Default")
      (node (ref "IC2") (pin "14") (pinfunction "PC4/OC1A/#SS_14") (pintype "bidirectional"))
      (node (ref "OUT10") (pin "K") (pinfunction "K_K") (pintype "bidirectional"))
    )
    (net (code "59") (name "OUT11") (class "Default")
      (node (ref "IC2") (pin "15") (pinfunction "PC5/OC1B/MOSI/XCK1_15") (pintype "bidirectional"))
      (node (ref "OUT11") (pin "K") (pinfunction "K_K") (pintype "bidirectional"))
    )
    (net (code "60") (name "OUT12") (class "Default")
      (node (ref "IC2") (pin "16") (pinfunction "PC6/MISO/RXD1_16") (pintype "bidirectional"))
      (node (ref "OUT12") (pin "K") (pinfunction "K_K") (pintype "bidirectional"))
    )
    (net (code "61") (name "OUT13") (class "Default")
      (node (ref "IC2") (pin "17") (pinfunction "PC7/SCK/TXD1/CLKO/EVO_17") (pintype "bidirectional"))
      (node (ref "OUT13") (pin "K") (pinfunction "K_K") (pintype "bidirectional"))
    )
    (net (code "62") (name "OUTPUT00") (class "Default")
      (node (ref "IC11") (pin "2") (pinfunction "P$2_2") (pintype "bidirectional"))
      (node (ref "IC2") (pin "10") (pinfunction "PC0/OC0A/SDA_10") (pintype "bidirectional"))
    )
    (net (code "63") (name "PDI-CLK") (class "Default")
      (node (ref "IC2") (pin "35") (pinfunction "RESET/PDI-CLK_35") (pintype "input"))
      (node (ref "PDI") (pin "P$3") (pinfunction "CLK_P$3") (pintype "bidirectional"))
    )
    (net (code "64") (name "PDI-DATA") (class "Default")
      (node (ref "IC2") (pin "34") (pinfunction "PDI-DATA_34") (pintype "bidirectional"))
      (node (ref "PDI") (pin "P$2") (pinfunction "DATA_P$2") (pintype "bidirectional"))
    )
    (net (code "65") (name "STATE") (class "Default")
      (node (ref "IC2") (pin "36") (pinfunction "PR0/XTAL2_36") (pintype "bidirectional"))
      (node (ref "R1") (pin "2") (pinfunction "2_2") (pintype "passive"))
    )
    (net (code "66") (name "USB5V") (class "Default")
      (node (ref "C1") (pin "2") (pinfunction "2_2") (pintype "passive"))
      (node (ref "C14") (pin "1") (pinfunction "1_1") (pintype "passive"))
      (node (ref "C15") (pin "+") (pinfunction "+_+") (pintype "passive"))
      (node (ref "C2") (pin "2") (pinfunction "2_2") (pintype "passive"))
      (node (ref "IC1") (pin "1") (pinfunction "IN_1") (pintype "bidirectional"))
      (node (ref "IC4") (pin "20") (pinfunction "VCC_20") (pintype "power_in"))
      (node (ref "L4") (pin "1") (pinfunction "1_1") (pintype "passive"))
      (node (ref "R10") (pin "1") (pinfunction "1_1") (pintype "passive"))
      (node (ref "R2") (pin "2") (pinfunction "2_2") (pintype "passive"))
      (node (ref "R3") (pin "2") (pinfunction "2_2") (pintype "passive"))
    )
    (net (code "67") (name "USBDM") (class "Default")
      (node (ref "C13") (pin "1") (pinfunction "1_1") (pintype "passive"))
      (node (ref "IC3") (pin "P$6") (pinfunction "IO1_P$6") (pintype "bidirectional"))
      (node (ref "IC4") (pin "16") (pinfunction "USBDM_16") (pintype "bidirectional"))
    )
    (net (code "68") (name "USBDP") (class "Default")
      (node (ref "C12") (pin "1") (pinfunction "1_1") (pintype "passive"))
      (node (ref "IC3") (pin "P$4") (pinfunction "IO2_P$4") (pintype "bidirectional"))
      (node (ref "IC4") (pin "15") (pinfunction "USBDP_15") (pintype "bidirectional"))
    )
    (net (code "69") (name "VCCIO") (class "Default")
      (node (ref "C10") (pin "1") (pinfunction "1_1") (pintype "passive"))
      (node (ref "C16") (pin "1") (pinfunction "1_1") (pintype "passive"))
      (node (ref "C18") (pin "1") (pinfunction "1_1") (pintype "passive"))
      (node (ref "C19") (pin "1") (pinfunction "1_1") (pintype "passive"))
      (node (ref "C20") (pin "1") (pinfunction "1_1") (pintype "passive"))
      (node (ref "C21") (pin "1") (pinfunction "1_1") (pintype "passive"))
      (node (ref "C22") (pin "1") (pinfunction "1_1") (pintype "passive"))
      (node (ref "C23") (pin "1") (pinfunction "1_1") (pintype "passive"))
      (node (ref "C25") (pin "1") (pinfunction "1_1") (pintype "passive"))
      (node (ref "C26") (pin "1") (pinfunction "1_1") (pintype "passive"))
      (node (ref "C27") (pin "1") (pinfunction "1_1") (pintype "passive"))
      (node (ref "C4") (pin "1") (pinfunction "1_1") (pintype "passive"))
      (node (ref "C5") (pin "1") (pinfunction "1_1") (pintype "passive"))
      (node (ref "C6") (pin "1") (pinfunction "1_1") (pintype "passive"))
      (node (ref "C7") (pin "1") (pinfunction "1_1") (pintype "passive"))
      (node (ref "C8") (pin "1") (pinfunction "1_1") (pintype "passive"))
      (node (ref "C9") (pin "1") (pinfunction "1_1") (pintype "passive"))
      (node (ref "CLKIN") (pin "1") (pinfunction "1_1") (pintype "passive"))
      (node (ref "IC1") (pin "5") (pinfunction "OUT_5") (pintype "bidirectional"))
      (node (ref "IC10") (pin "5") (pinfunction "P$5_5") (pintype "bidirectional"))
      (node (ref "IC12") (pin "5") (pinfunction "P$5_5") (pintype "bidirectional"))
      (node (ref "IC13") (pin "5") (pinfunction "P$5_5") (pintype "bidirectional"))
      (node (ref "IC14") (pin "5") (pinfunction "P$5_5") (pintype "bidirectional"))
      (node (ref "IC2") (pin "19") (pinfunction "VCC_19") (pintype "power_in"))
      (node (ref "IC2") (pin "31") (pinfunction "VCC_31") (pintype "power_in"))
      (node (ref "IC2") (pin "39") (pinfunction "AVCC_39") (pintype "power_in"))
      (node (ref "IC2") (pin "9") (pinfunction "VCC_9") (pintype "power_in"))
      (node (ref "IC4") (pin "4") (pinfunction "VCCIO_4") (pintype "power_in"))
      (node (ref "IC5") (pin "5") (pinfunction "P$5_5") (pintype "bidirectional"))
      (node (ref "IC6") (pin "5") (pinfunction "P$5_5") (pintype "bidirectional"))
      (node (ref "IC7") (pin "5") (pinfunction "P$5_5") (pintype "bidirectional"))
      (node (ref "IC8") (pin "5") (pinfunction "P$5_5") (pintype "bidirectional"))
      (node (ref "IC9") (pin "5") (pinfunction "P$5_5") (pintype "bidirectional"))
      (node (ref "OSC1") (pin "P$4") (pinfunction "VDD_P$4") (pintype "passive"))
      (node (ref "PDI") (pin "P$4") (pinfunction "VCC_P$4") (pintype "bidirectional"))
      (node (ref "R14") (pin "2") (pinfunction "2_2") (pintype "passive"))
      (node (ref "R15") (pin "2") (pinfunction "2_2") (pintype "passive"))
      (node (ref "R16") (pin "2") (pinfunction "2_2") (pintype "passive"))
      (node (ref "R17") (pin "2") (pinfunction "2_2") (pintype "passive"))
      (node (ref "R18") (pin "2") (pinfunction "2_2") (pintype "passive"))
      (node (ref "R19") (pin "2") (pinfunction "2_2") (pintype "passive"))
      (node (ref "R20") (pin "2") (pinfunction "2_2") (pintype "passive"))
      (node (ref "R21") (pin "2") (pinfunction "2_2") (pintype "passive"))
      (node (ref "R22") (pin "2") (pinfunction "2_2") (pintype "passive"))
      (node (ref "R23") (pin "2") (pinfunction "2_2") (pintype "passive"))
      (node (ref "R24") (pin "1") (pinfunction "1_1") (pintype "passive"))
    )
    (net (code "70") (name "unconnected-(A0-Pad3)") (class "Default")
      (node (ref "A0") (pin "3") (pinfunction "3_3") (pintype "passive"))
    )
    (net (code "71") (name "unconnected-(A1-Pad3)") (class "Default")
      (node (ref "A1") (pin "3") (pinfunction "3_3") (pintype "passive"))
    )
    (net (code "72") (name "unconnected-(IC1-EN-Pad3)") (class "Default")
      (node (ref "IC1") (pin "3") (pinfunction "EN_3") (pintype "bidirectional"))
    )
    (net (code "73") (name "unconnected-(IC2-PA6{slash}ADC6-Pad2)") (class "Default")
      (node (ref "IC2") (pin "2") (pinfunction "PA6/ADC6_2") (pintype "bidirectional"))
    )
    (net (code "74") (name "unconnected-(IC2-PB3{slash}ADC11{slash}DAC1-Pad7)") (class "Default")
      (node (ref "IC2") (pin "7") (pinfunction "PB3/ADC11/DAC1_7") (pintype "bidirectional"))
    )
    (net (code "75") (name "unconnected-(IC2-PC3{slash}OC0D{slash}TXD0-Pad13)") (class "Default")
      (node (ref "IC2") (pin "13") (pinfunction "PC3/OC0D/TXD0_13") (pintype "bidirectional"))
    )
    (net (code "76") (name "unconnected-(IC2-~RXD1MISOPD6-Pad26)") (class "Default")
      (node (ref "IC2") (pin "26") (pinfunction "~RXD1MISOPD6_26") (pintype "bidirectional"))
    )
    (net (code "77") (name "unconnected-(IC2-~~{TXD1SCKCLKOPD7}-Pad27)") (class "Default")
      (node (ref "IC2") (pin "27") (pinfunction "~~{TXD1SCKCLKOPD7}_27") (pintype "bidirectional"))
    )
    (net (code "78") (name "unconnected-(IC4-CBUS2-Pad13)") (class "Default")
      (node (ref "IC4") (pin "13") (pinfunction "CBUS2_13") (pintype "bidirectional"))
    )
    (net (code "79") (name "unconnected-(IC4-CBUS3-Pad14)") (class "Default")
      (node (ref "IC4") (pin "14") (pinfunction "CBUS3_14") (pintype "bidirectional"))
    )
    (net (code "80") (name "unconnected-(IC4-CBUS4-Pad12)") (class "Default")
      (node (ref "IC4") (pin "12") (pinfunction "CBUS4_12") (pintype "bidirectional"))
    )
    (net (code "81") (name "unconnected-(IC4-OSCI-Pad27)") (class "Default")
      (node (ref "IC4") (pin "27") (pinfunction "OSCI_27") (pintype "input"))
    )
    (net (code "82") (name "unconnected-(IC4-OSCO-Pad28)") (class "Default")
      (node (ref "IC4") (pin "28") (pinfunction "OSCO_28") (pintype "output"))
    )
    (net (code "83") (name "unconnected-(IC4-~{DCD}-Pad10)") (class "Default")
      (node (ref "IC4") (pin "10") (pinfunction "~{DCD}_10") (pintype "input"))
    )
    (net (code "84") (name "unconnected-(IC4-~{DSR}-Pad9)") (class "Default")
      (node (ref "IC4") (pin "9") (pinfunction "~{DSR}_9") (pintype "input"))
    )
    (net (code "85") (name "unconnected-(IC4-~{DTR}-Pad2)") (class "Default")
      (node (ref "IC4") (pin "2") (pinfunction "~{DTR}_2") (pintype "output"))
    )
    (net (code "86") (name "unconnected-(IC4-~{RESET}-Pad19)") (class "Default")
      (node (ref "IC4") (pin "19") (pinfunction "~{RESET}_19") (pintype "input"))
    )
    (net (code "87") (name "unconnected-(IC4-~{RI}-Pad6)") (class "Default")
      (node (ref "IC4") (pin "6") (pinfunction "~{RI}_6") (pintype "input"))
    )
    (net (code "88") (name "unconnected-(OSC1-STANDBY#-PadP$1)") (class "Default")
      (node (ref "OSC1") (pin "P$1") (pinfunction "STANDBY#_P$1") (pintype "passive"))
    )
    (net (code "89") (name "unconnected-(USB-4-PadP$4)") (class "Default")
      (node (ref "USB") (pin "P$4") (pinfunction "4_P$4") (pintype "bidirectional"))
    )
    (net (code "90") (name "unconnected-(USB-P$2-PadSHIELD_2)") (class "Default")
      (node (ref "USB") (pin "SHIELD_2") (pinfunction "P$2_SHIELD_2") (pintype "bidirectional"))
    )
    (net (code "91") (name "unconnected-(USB-P$3-PadSHIELD_3)") (class "Default")
      (node (ref "USB") (pin "SHIELD_3") (pinfunction "P$3_SHIELD_3") (pintype "bidirectional"))
    )
  )
)
